# Sheet1.net
KiCad netlist of a schematic drawn in Altium Designer
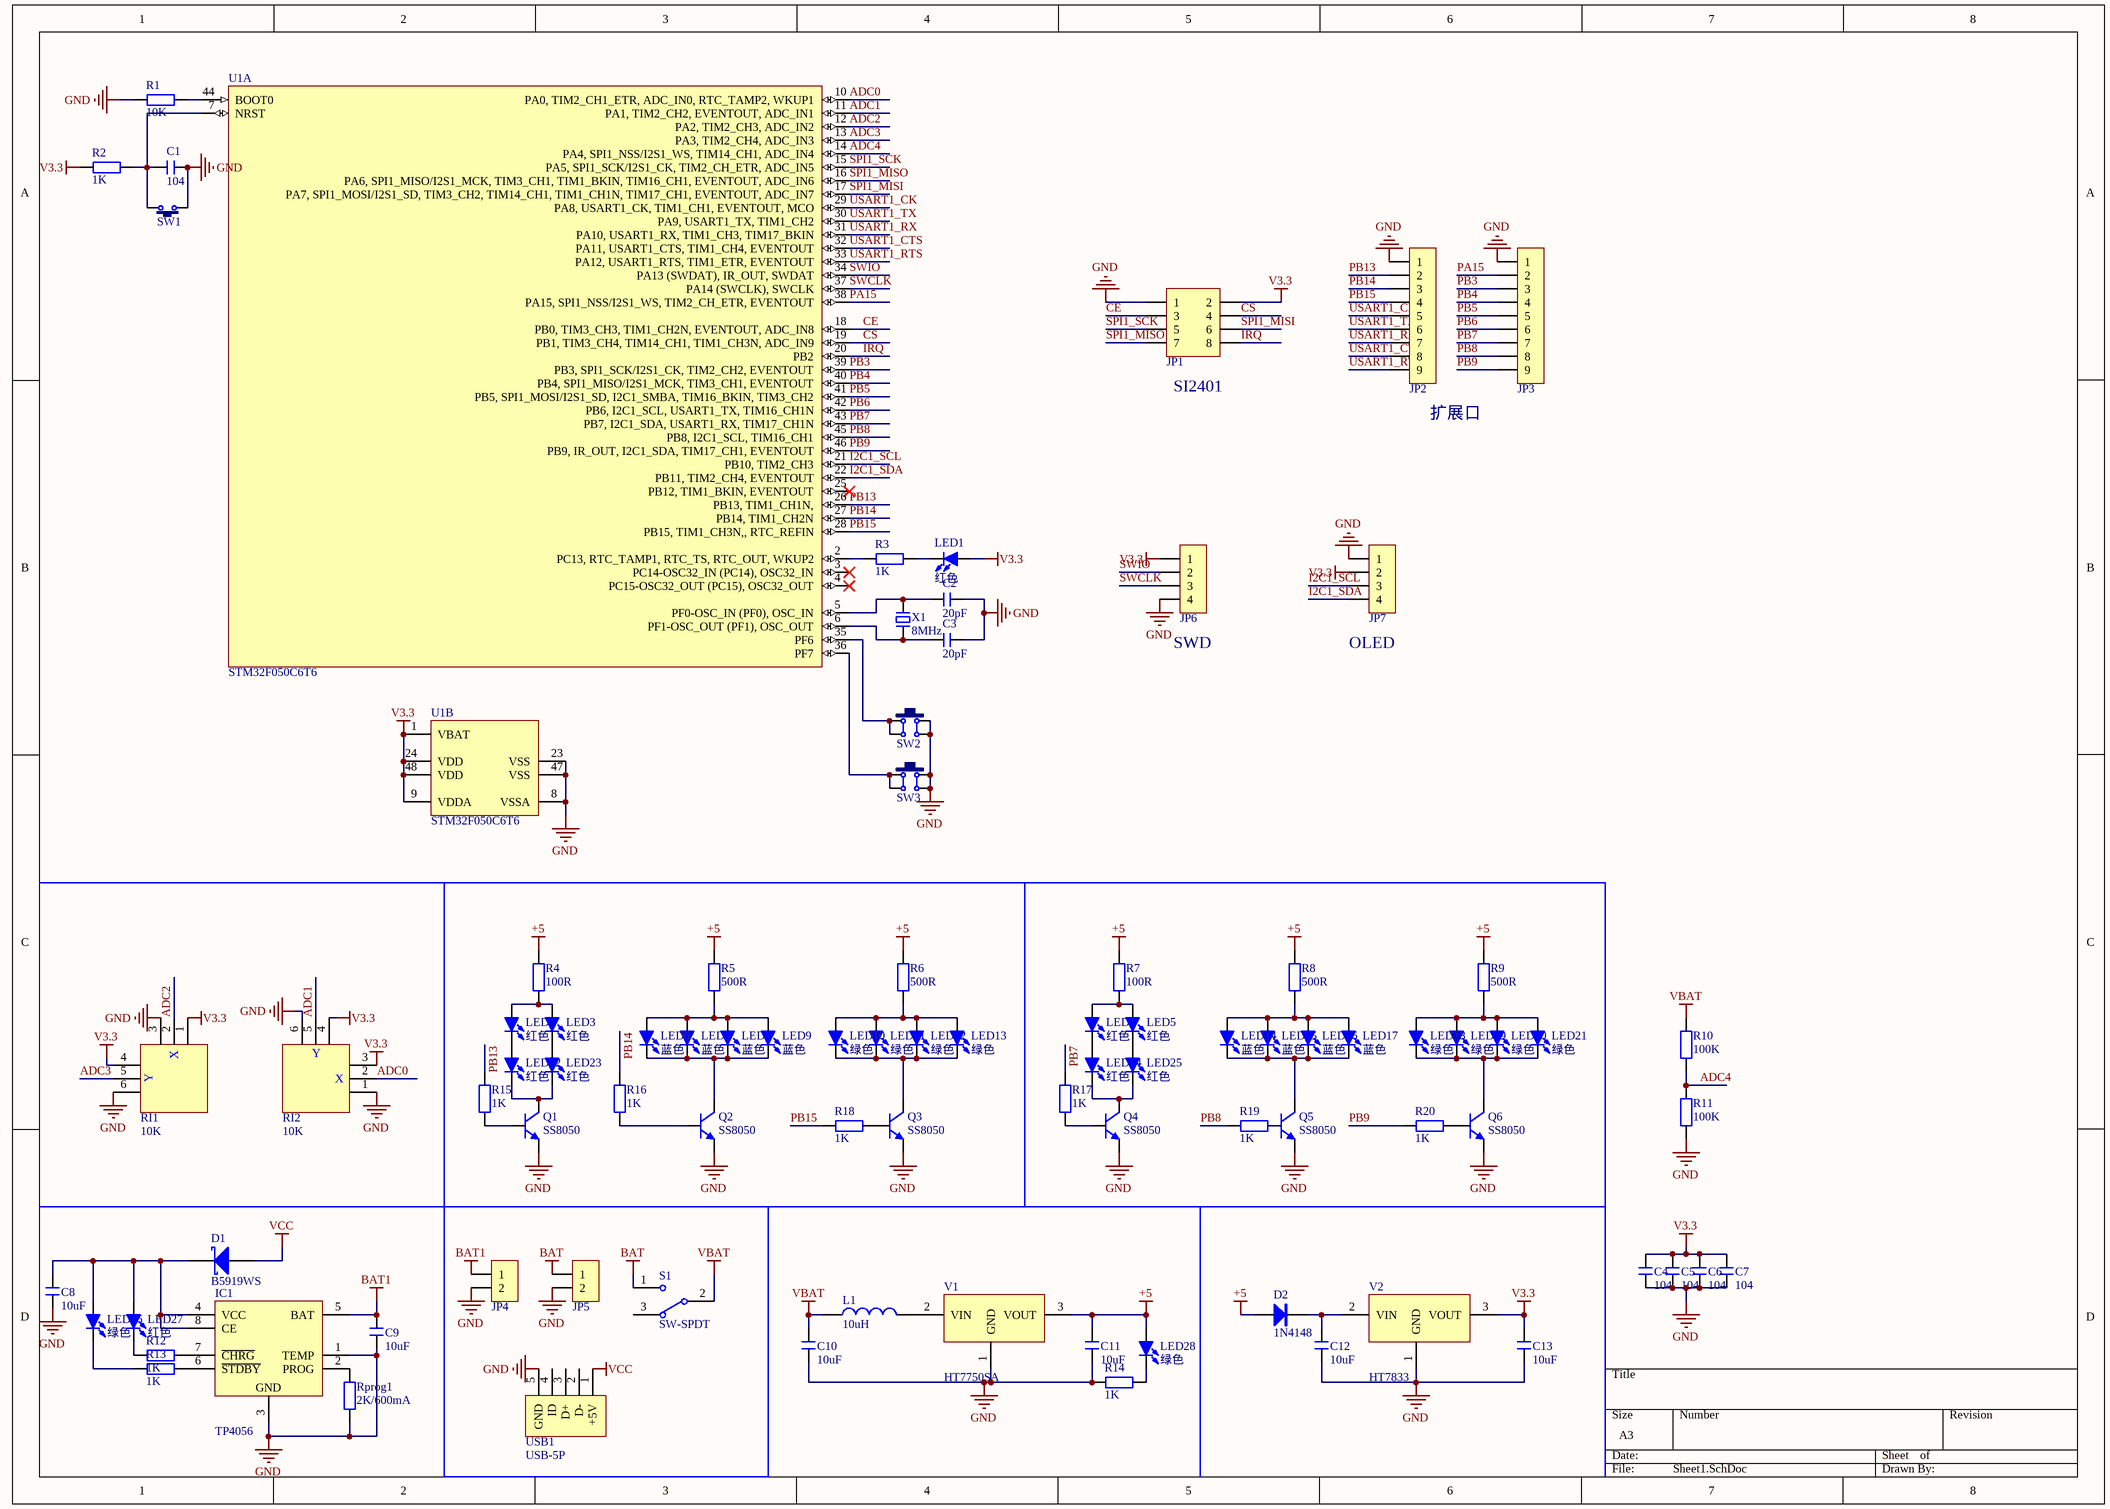
[diagram p0: Sheet1.SchDoc]

(export (version "E")
  (design (tool "Eeschema 10.0.6"))
  (components
    (comp (ref "C1")
      (value "104")
      (footprint "C 0603_L")
      (description "贴片电容")
      (libsource (lib "0.1 - 电阻-电容-电感") (part "C"))
    )
    (comp (ref "C2")
      (value "20pF")
      (footprint "C 0805_L")
      (description "贴片电容")
      (libsource (lib "0.1 - 电阻-电容-电感") (part "C"))
    )
    (comp (ref "C3")
      (value "20pF")
      (footprint "C 0805_L")
      (description "贴片电容")
      (libsource (lib "0.1 - 电阻-电容-电感") (part "C"))
    )
    (comp (ref "C4")
      (value "104")
      (footprint "C 0603_L")
      (description "贴片电容")
      (libsource (lib "0.1 - 电阻-电容-电感") (part "C"))
    )
    (comp (ref "C5")
      (value "104")
      (footprint "C 0603_L")
      (description "贴片电容")
      (libsource (lib "0.1 - 电阻-电容-电感") (part "C"))
    )
    (comp (ref "C6")
      (value "104")
      (footprint "C 0603_L")
      (description "贴片电容")
      (libsource (lib "0.1 - 电阻-电容-电感") (part "C"))
    )
    (comp (ref "C7")
      (value "104")
      (footprint "C 0603_L")
      (description "贴片电容")
      (libsource (lib "0.1 - 电阻-电容-电感") (part "C"))
    )
    (comp (ref "C8")
      (value "10uF")
      (footprint "C 0603_L")
      (description "贴片电容")
      (libsource (lib "0.1 - 电阻-电容-电感") (part "C"))
    )
    (comp (ref "C9")
      (value "10uF")
      (footprint "C 0603_L")
      (description "贴片电容")
      (libsource (lib "0.1 - 电阻-电容-电感") (part "C"))
    )
    (comp (ref "C10")
      (value "10uF")
      (footprint "C 0603_L")
      (description "贴片电容")
      (libsource (lib "0.1 - 电阻-电容-电感") (part "C"))
    )
    (comp (ref "C11")
      (value "10uF")
      (footprint "C 0603_L")
      (description "贴片电容")
      (libsource (lib "0.1 - 电阻-电容-电感") (part "C"))
    )
    (comp (ref "C12")
      (value "10uF")
      (footprint "C 0603_L")
      (description "贴片电容")
      (libsource (lib "0.1 - 电阻-电容-电感") (part "C"))
    )
    (comp (ref "C13")
      (value "10uF")
      (footprint "C 0603_L")
      (description "贴片电容")
      (libsource (lib "0.1 - 电阻-电容-电感") (part "C"))
    )
    (comp (ref "D1")
      (value "B5919WS")
      (footprint "SOD-323")
      (description "肖特基二极管")
      (libsource (lib "0.2 -  二极管-整流桥") (part "1N5819"))
    )
    (comp (ref "D2")
      (value "1N4148")
      (footprint "MINI_MELF (LL34)")
      (description "开关二极管")
      (libsource (lib "0.2 -  二极管-整流桥") (part "1N4148"))
    )
    (comp (ref "IC1")
      (value "TP4056")
      (footprint "SOP8_N")
      (description "锂电池充电管理")
      (libsource (lib "1.1 - 电源类芯片") (part "TP4056"))
    )
    (comp (ref "JP1")
      (value "Header 4X2")
      (footprint "HDR2.54-LI-2x4P")
      (description "4*2P接插件")
      (fields (field (name "版权归属") "封装库来自淘宝 ID：黄晶宝石"))
      (libsource (lib "5.3 - 接插件-脚距2.54 (100mil) ") (part "Header 4X2"))
    )
    (comp (ref "JP2")
      (value "HDR-1X9")
      (footprint "HDR2.54-LI-9P")
      (description "9P接插件")
      (fields (field (name "版权归属") "源创客"))
      (libsource (lib "5.3 - 接插件-脚距2.54 (100mil) ") (part "Header 9"))
    )
    (comp (ref "JP3")
      (value "HDR-1X9")
      (footprint "HDR2.54-LI-9P")
      (description "9P接插件")
      (fields (field (name "版权归属") "源创客"))
      (libsource (lib "5.3 - 接插件-脚距2.54 (100mil) ") (part "Header 9"))
    )
    (comp (ref "JP4")
      (value "HDR-1X2")
      (footprint "XH2.54-LI-2P")
      (description "2P接插件")
      (fields (field (name "版权归属") "封装库来自淘宝 ID：黄晶宝石"))
      (libsource (lib "5.3 - 接插件-脚距2.54 (100mil) ") (part "Header 2"))
    )
    (comp (ref "JP5")
      (value "HDR-1X2")
      (footprint "XH2.54-LI-2P")
      (description "2P接插件")
      (fields (field (name "版权归属") "封装库来自淘宝 ID：黄晶宝石"))
      (libsource (lib "5.3 - 接插件-脚距2.54 (100mil) ") (part "Header 2"))
    )
    (comp (ref "JP6")
      (value "HDR-1X4")
      (footprint "HDR2.54-LI-4P")
      (description "4P接插件")
      (fields (field (name "版权归属") "封装库来自淘宝 ID：黄晶宝石"))
      (libsource (lib "5.3 - 接插件-脚距2.54 (100mil) ") (part "Header 4"))
    )
    (comp (ref "JP7")
      (value "HDR-1X4")
      (footprint "HDR2.54-M-LI-4P")
      (description "4P接插件")
      (fields (field (name "版权归属") "封装库来自淘宝 ID：黄晶宝石"))
      (libsource (lib "5.3 - 接插件-脚距2.54 (100mil) ") (part "Header 4"))
    )
    (comp (ref "L1")
      (value "10uH")
      (footprint "L 0805")
      (description "小功率贴片电感")
      (libsource (lib "0.1 - 电阻-电容-电感") (part "L"))
    )
    (comp (ref "LED1")
      (value "红色")
      (footprint "LED 0603R")
      (description "贴片LED")
      (fields (field (name "版权归属") "封装库来自淘宝 ID：黄晶宝石"))
      (libsource (lib "0.3 - LED发光二极管") (part "LED-SMD"))
    )
    (comp (ref "LED2")
      (value "红色")
      (footprint "LED 0603R")
      (description "贴片LED")
      (fields (field (name "版权归属") "封装库来自淘宝 ID：黄晶宝石"))
      (libsource (lib "0.3 - LED发光二极管") (part "LED-SMD"))
    )
    (comp (ref "LED3")
      (value "红色")
      (footprint "LED 0603R")
      (description "贴片LED")
      (fields (field (name "版权归属") "封装库来自淘宝 ID：黄晶宝石"))
      (libsource (lib "0.3 - LED发光二极管") (part "LED-SMD"))
    )
    (comp (ref "LED4")
      (value "红色")
      (footprint "LED 0603R")
      (description "贴片LED")
      (fields (field (name "版权归属") "封装库来自淘宝 ID：黄晶宝石"))
      (libsource (lib "0.3 - LED发光二极管") (part "LED-SMD"))
    )
    (comp (ref "LED5")
      (value "红色")
      (footprint "LED 0603R")
      (description "贴片LED")
      (fields (field (name "版权归属") "封装库来自淘宝 ID：黄晶宝石"))
      (libsource (lib "0.3 - LED发光二极管") (part "LED-SMD"))
    )
    (comp (ref "LED6")
      (value "蓝色")
      (footprint "LED 0603B")
      (description "贴片LED")
      (fields (field (name "版权归属") "封装库来自淘宝 ID：黄晶宝石"))
      (libsource (lib "0.3 - LED发光二极管") (part "LED-SMD"))
    )
    (comp (ref "LED7")
      (value "蓝色")
      (footprint "LED 0603B")
      (description "贴片LED")
      (fields (field (name "版权归属") "封装库来自淘宝 ID：黄晶宝石"))
      (libsource (lib "0.3 - LED发光二极管") (part "LED-SMD"))
    )
    (comp (ref "LED8")
      (value "蓝色")
      (footprint "LED 0603B")
      (description "贴片LED")
      (fields (field (name "版权归属") "封装库来自淘宝 ID：黄晶宝石"))
      (libsource (lib "0.3 - LED发光二极管") (part "LED-SMD"))
    )
    (comp (ref "LED9")
      (value "蓝色")
      (footprint "LED 0603B")
      (description "贴片LED")
      (fields (field (name "版权归属") "封装库来自淘宝 ID：黄晶宝石"))
      (libsource (lib "0.3 - LED发光二极管") (part "LED-SMD"))
    )
    (comp (ref "LED10")
      (value "绿色")
      (footprint "LED 0603G")
      (description "贴片LED")
      (fields (field (name "版权归属") "封装库来自淘宝 ID：黄晶宝石"))
      (libsource (lib "0.3 - LED发光二极管") (part "LED-SMD"))
    )
    (comp (ref "LED11")
      (value "绿色")
      (footprint "LED 0603G")
      (description "贴片LED")
      (fields (field (name "版权归属") "封装库来自淘宝 ID：黄晶宝石"))
      (libsource (lib "0.3 - LED发光二极管") (part "LED-SMD"))
    )
    (comp (ref "LED12")
      (value "绿色")
      (footprint "LED 0603G")
      (description "贴片LED")
      (fields (field (name "版权归属") "封装库来自淘宝 ID：黄晶宝石"))
      (libsource (lib "0.3 - LED发光二极管") (part "LED-SMD"))
    )
    (comp (ref "LED13")
      (value "绿色")
      (footprint "LED 0603G")
      (description "贴片LED")
      (fields (field (name "版权归属") "封装库来自淘宝 ID：黄晶宝石"))
      (libsource (lib "0.3 - LED发光二极管") (part "LED-SMD"))
    )
    (comp (ref "LED14")
      (value "蓝色")
      (footprint "LED 0603B")
      (description "贴片LED")
      (fields (field (name "版权归属") "封装库来自淘宝 ID：黄晶宝石"))
      (libsource (lib "0.3 - LED发光二极管") (part "LED-SMD"))
    )
    (comp (ref "LED15")
      (value "蓝色")
      (footprint "LED 0603B")
      (description "贴片LED")
      (fields (field (name "版权归属") "封装库来自淘宝 ID：黄晶宝石"))
      (libsource (lib "0.3 - LED发光二极管") (part "LED-SMD"))
    )
    (comp (ref "LED16")
      (value "蓝色")
      (footprint "LED 0603B")
      (description "贴片LED")
      (fields (field (name "版权归属") "封装库来自淘宝 ID：黄晶宝石"))
      (libsource (lib "0.3 - LED发光二极管") (part "LED-SMD"))
    )
    (comp (ref "LED17")
      (value "蓝色")
      (footprint "LED 0603B")
      (description "贴片LED")
      (fields (field (name "版权归属") "封装库来自淘宝 ID：黄晶宝石"))
      (libsource (lib "0.3 - LED发光二极管") (part "LED-SMD"))
    )
    (comp (ref "LED18")
      (value "绿色")
      (footprint "LED 0603G")
      (description "贴片LED")
      (fields (field (name "版权归属") "封装库来自淘宝 ID：黄晶宝石"))
      (libsource (lib "0.3 - LED发光二极管") (part "LED-SMD"))
    )
    (comp (ref "LED19")
      (value "绿色")
      (footprint "LED 0603G")
      (description "贴片LED")
      (fields (field (name "版权归属") "封装库来自淘宝 ID：黄晶宝石"))
      (libsource (lib "0.3 - LED发光二极管") (part "LED-SMD"))
    )
    (comp (ref "LED20")
      (value "绿色")
      (footprint "LED 0603G")
      (description "贴片LED")
      (fields (field (name "版权归属") "封装库来自淘宝 ID：黄晶宝石"))
      (libsource (lib "0.3 - LED发光二极管") (part "LED-SMD"))
    )
    (comp (ref "LED21")
      (value "绿色")
      (footprint "LED 0603G")
      (description "贴片LED")
      (fields (field (name "版权归属") "封装库来自淘宝 ID：黄晶宝石"))
      (libsource (lib "0.3 - LED发光二极管") (part "LED-SMD"))
    )
    (comp (ref "LED22")
      (value "红色")
      (footprint "LED 0603R")
      (description "贴片LED")
      (fields (field (name "版权归属") "封装库来自淘宝 ID：黄晶宝石"))
      (libsource (lib "0.3 - LED发光二极管") (part "LED-SMD"))
    )
    (comp (ref "LED23")
      (value "红色")
      (footprint "LED 0603R")
      (description "贴片LED")
      (fields (field (name "版权归属") "封装库来自淘宝 ID：黄晶宝石"))
      (libsource (lib "0.3 - LED发光二极管") (part "LED-SMD"))
    )
    (comp (ref "LED24")
      (value "红色")
      (footprint "LED 0603R")
      (description "贴片LED")
      (fields (field (name "版权归属") "封装库来自淘宝 ID：黄晶宝石"))
      (libsource (lib "0.3 - LED发光二极管") (part "LED-SMD"))
    )
    (comp (ref "LED25")
      (value "红色")
      (footprint "LED 0603R")
      (description "贴片LED")
      (fields (field (name "版权归属") "封装库来自淘宝 ID：黄晶宝石"))
      (libsource (lib "0.3 - LED发光二极管") (part "LED-SMD"))
    )
    (comp (ref "LED26")
      (value "绿色")
      (footprint "LED 0603G")
      (description "贴片LED")
      (fields (field (name "版权归属") "封装库来自淘宝 ID：黄晶宝石"))
      (libsource (lib "0.3 - LED发光二极管") (part "LED-SMD"))
    )
    (comp (ref "LED27")
      (value "红色")
      (footprint "LED 0603R")
      (description "贴片LED")
      (fields (field (name "版权归属") "封装库来自淘宝 ID：黄晶宝石"))
      (libsource (lib "0.3 - LED发光二极管") (part "LED-SMD"))
    )
    (comp (ref "LED28")
      (value "绿色")
      (footprint "LED 0603G")
      (description "贴片LED")
      (fields (field (name "版权归属") "封装库来自淘宝 ID：黄晶宝石"))
      (libsource (lib "0.3 - LED发光二极管") (part "LED-SMD"))
    )
    (comp (ref "Q1")
      (value "SS8050")
      (footprint "SOT23-3N")
      (description "高频放大-NPN型")
      (fields (field (name "版权归属") "封装库来自淘宝 ID：黄晶宝石"))
      (libsource (lib "0.4 - 三极管") (part "8050-SMD"))
    )
    (comp (ref "Q2")
      (value "SS8050")
      (footprint "SOT23-3N")
      (description "高频放大-NPN型")
      (fields (field (name "版权归属") "封装库来自淘宝 ID：黄晶宝石"))
      (libsource (lib "0.4 - 三极管") (part "8050-SMD"))
    )
    (comp (ref "Q3")
      (value "SS8050")
      (footprint "SOT23-3N")
      (description "高频放大-NPN型")
      (fields (field (name "版权归属") "封装库来自淘宝 ID：黄晶宝石"))
      (libsource (lib "0.4 - 三极管") (part "8050-SMD"))
    )
    (comp (ref "Q4")
      (value "SS8050")
      (footprint "SOT23-3N")
      (description "高频放大-NPN型")
      (fields (field (name "版权归属") "封装库来自淘宝 ID：黄晶宝石"))
      (libsource (lib "0.4 - 三极管") (part "8050-SMD"))
    )
    (comp (ref "Q5")
      (value "SS8050")
      (footprint "SOT23-3N")
      (description "高频放大-NPN型")
      (fields (field (name "版权归属") "封装库来自淘宝 ID：黄晶宝石"))
      (libsource (lib "0.4 - 三极管") (part "8050-SMD"))
    )
    (comp (ref "Q6")
      (value "SS8050")
      (footprint "SOT23-3N")
      (description "高频放大-NPN型")
      (fields (field (name "版权归属") "封装库来自淘宝 ID：黄晶宝石"))
      (libsource (lib "0.4 - 三极管") (part "8050-SMD"))
    )
    (comp (ref "R1")
      (value "10K")
      (footprint "R 0603_L")
      (description "贴片电阻")
      (fields (field (name "版权归属") "来自淘宝 ID：黄晶宝石"))
      (libsource (lib "0.1 - 电阻-电容-电感") (part "R"))
    )
    (comp (ref "R2")
      (value "1K")
      (footprint "R 0603_L")
      (description "贴片电阻")
      (fields (field (name "版权归属") "来自淘宝 ID：黄晶宝石"))
      (libsource (lib "0.1 - 电阻-电容-电感") (part "R"))
    )
    (comp (ref "R3")
      (value "1K")
      (footprint "R 0603_L")
      (description "贴片电阻")
      (fields (field (name "版权归属") "来自淘宝 ID：黄晶宝石"))
      (libsource (lib "0.1 - 电阻-电容-电感") (part "R"))
    )
    (comp (ref "R4")
      (value "100R")
      (footprint "R 0603_L")
      (description "贴片电阻")
      (fields (field (name "版权归属") "来自淘宝 ID：黄晶宝石"))
      (libsource (lib "0.1 - 电阻-电容-电感") (part "R"))
    )
    (comp (ref "R5")
      (value "500R")
      (footprint "R 0603_L")
      (description "贴片电阻")
      (fields (field (name "版权归属") "来自淘宝 ID：黄晶宝石"))
      (libsource (lib "0.1 - 电阻-电容-电感") (part "R"))
    )
    (comp (ref "R6")
      (value "500R")
      (footprint "R 0603_L")
      (description "贴片电阻")
      (fields (field (name "版权归属") "来自淘宝 ID：黄晶宝石"))
      (libsource (lib "0.1 - 电阻-电容-电感") (part "R"))
    )
    (comp (ref "R7")
      (value "100R")
      (footprint "R 0603_L")
      (description "贴片电阻")
      (fields (field (name "版权归属") "来自淘宝 ID：黄晶宝石"))
      (libsource (lib "0.1 - 电阻-电容-电感") (part "R"))
    )
    (comp (ref "R8")
      (value "500R")
      (footprint "R 0603_L")
      (description "贴片电阻")
      (fields (field (name "版权归属") "来自淘宝 ID：黄晶宝石"))
      (libsource (lib "0.1 - 电阻-电容-电感") (part "R"))
    )
    (comp (ref "R9")
      (value "500R")
      (footprint "R 0603_L")
      (description "贴片电阻")
      (fields (field (name "版权归属") "来自淘宝 ID：黄晶宝石"))
      (libsource (lib "0.1 - 电阻-电容-电感") (part "R"))
    )
    (comp (ref "R10")
      (value "100K")
      (footprint "R 0603_L")
      (description "贴片电阻")
      (fields (field (name "版权归属") "来自淘宝 ID：黄晶宝石"))
      (libsource (lib "0.1 - 电阻-电容-电感") (part "R"))
    )
    (comp (ref "R11")
      (value "100K")
      (footprint "R 0603_L")
      (description "贴片电阻")
      (fields (field (name "版权归属") "来自淘宝 ID：黄晶宝石"))
      (libsource (lib "0.1 - 电阻-电容-电感") (part "R"))
    )
    (comp (ref "R12")
      (value "1K")
      (footprint "R 0603_L")
      (description "贴片电阻")
      (fields (field (name "版权归属") "来自淘宝 ID：黄晶宝石"))
      (libsource (lib "0.1 - 电阻-电容-电感") (part "R"))
    )
    (comp (ref "R13")
      (value "1K")
      (footprint "R 0603_L")
      (description "贴片电阻")
      (fields (field (name "版权归属") "来自淘宝 ID：黄晶宝石"))
      (libsource (lib "0.1 - 电阻-电容-电感") (part "R"))
    )
    (comp (ref "R14")
      (value "1K")
      (footprint "R 0603_L")
      (description "贴片电阻")
      (fields (field (name "版权归属") "来自淘宝 ID：黄晶宝石"))
      (libsource (lib "0.1 - 电阻-电容-电感") (part "R"))
    )
    (comp (ref "R15")
      (value "1K")
      (footprint "R 0603_L")
      (description "贴片电阻")
      (fields (field (name "版权归属") "来自淘宝 ID：黄晶宝石"))
      (libsource (lib "0.1 - 电阻-电容-电感") (part "R"))
    )
    (comp (ref "R16")
      (value "1K")
      (footprint "R 0603_L")
      (description "贴片电阻")
      (fields (field (name "版权归属") "来自淘宝 ID：黄晶宝石"))
      (libsource (lib "0.1 - 电阻-电容-电感") (part "R"))
    )
    (comp (ref "R17")
      (value "1K")
      (footprint "R 0603_L")
      (description "贴片电阻")
      (fields (field (name "版权归属") "来自淘宝 ID：黄晶宝石"))
      (libsource (lib "0.1 - 电阻-电容-电感") (part "R"))
    )
    (comp (ref "R18")
      (value "1K")
      (footprint "R 0603_L")
      (description "贴片电阻")
      (fields (field (name "版权归属") "来自淘宝 ID：黄晶宝石"))
      (libsource (lib "0.1 - 电阻-电容-电感") (part "R"))
    )
    (comp (ref "R19")
      (value "1K")
      (footprint "R 0603_L")
      (description "贴片电阻")
      (fields (field (name "版权归属") "来自淘宝 ID：黄晶宝石"))
      (libsource (lib "0.1 - 电阻-电容-电感") (part "R"))
    )
    (comp (ref "R20")
      (value "1K")
      (footprint "R 0603_L")
      (description "贴片电阻")
      (fields (field (name "版权归属") "来自淘宝 ID：黄晶宝石"))
      (libsource (lib "0.1 - 电阻-电容-电感") (part "R"))
    )
    (comp (ref "RI1")
      (value "10K")
      (footprint "ROC16")
      (description "摇杆电位器")
      (fields (field (name "版权归属") "封装库来自淘宝 ID：黄晶宝石"))
      (libsource (lib "") (part "ROC16B_1"))
    )
    (comp (ref "RI2")
      (value "10K")
      (footprint "ROC16")
      (description "摇杆电位器")
      (fields (field (name "版权归属") "封装库来自淘宝 ID：黄晶宝石"))
      (libsource (lib "1.2 - 传感元件") (part "ROC16B"))
    )
    (comp (ref "Rprog1")
      (value "2K/600mA")
      (footprint "R 0603_M")
      (description "贴片电阻")
      (fields (field (name "版权归属") "来自淘宝 ID：黄晶宝石"))
      (libsource (lib "0.1 - 电阻-电容-电感") (part "R"))
    )
    (comp (ref "S1")
      (value "SW-SPDT")
      (footprint "SWITCH_PWR")
      (description "SPDT Subminiature Toggle Switch, Right Angle Mounting, Vertical Actuation")
      (fields (field (name "PUBLISHER") "mazhongwei"))
      (libsource (lib "RoboFly") (part "SW-SPDT"))
    )
    (comp (ref "SW1")
      (value "3x6x5")
      (footprint "TSW SMD-3*6*2.5")
      (description "3x6轻触开关")
      (fields (field (name "版权归属") "封装库来自淘宝 ID：黄晶宝石"))
      (libsource (lib "0.7 - 常用按键-开关") (part "TSW 3x6"))
    )
    (comp (ref "SW2")
      (value "6x6x5")
      (footprint "TSW DIP-6*6*6")
      (description "直插6x6轻触开关")
      (fields (field (name "版权归属") "封装库来自淘宝 ID：黄晶宝石"))
      (libsource (lib "0.7 - 常用按键-开关") (part "TSW DIP-6x6"))
    )
    (comp (ref "SW3")
      (value "6x6x5")
      (footprint "TSW DIP-6*6*6")
      (description "直插6x6轻触开关")
      (fields (field (name "版权归属") "封装库来自淘宝 ID：黄晶宝石"))
      (libsource (lib "0.7 - 常用按键-开关") (part "TSW DIP-6x6"))
    )
    (comp (ref "U1")
      (value "STM32F050C6T6")
      (footprint "LQFP48_N")
      (libsource (lib "2.2 - STM32 F0系列MCU 集成库") (part "STM32F050C6T6"))
    )
    (comp (ref "USB1")
      (value "USB-5P")
      (footprint "USB-MICRO_D")
      (description "微型USB母座")
      (libsource (lib "0.8 - 网口-音频插座") (part "USB-5P"))
    )
    (comp (ref "V1")
      (value "HT7750SA")
      (footprint "SOT89_M")
      (description "LDO线性稳压芯片")
      (fields (field (name "版权归属") "封装库来自淘宝 ID：黄晶宝石"))
      (libsource (lib "1.1 - 电源类芯片") (part "HT71xx"))
    )
    (comp (ref "V2")
      (value "HT7833")
      (footprint "SOT89_M")
      (description "LDO线性稳压芯片")
      (fields (field (name "版权归属") "封装库来自淘宝 ID：黄晶宝石"))
      (libsource (lib "1.1 - 电源类芯片") (part "HT71xx"))
    )
    (comp (ref "X1")
      (value "8MHz")
      (footprint "OSC HC-49S")
      (description "2脚无源脚晶振")
      (fields (field (name "版权归属") "源创客"))
      (libsource (lib "2.0 - 保险丝-晶振-光耦") (part "XTAL-2P"))
    )
  )
  (nets
    (net (code "1") (name "+5") (class "Default")
      (node (ref "C11") (pin "2") (pinfunction "2_2") (pintype "passive"))
      (node (ref "D2") (pin "1") (pinfunction "A_1") (pintype "passive"))
      (node (ref "LED28") (pin "1") (pinfunction "A_1") (pintype "passive"))
      (node (ref "R4") (pin "2") (pinfunction "2_2") (pintype "passive"))
      (node (ref "R5") (pin "2") (pinfunction "2_2") (pintype "passive"))
      (node (ref "R6") (pin "2") (pinfunction "2_2") (pintype "passive"))
      (node (ref "R7") (pin "2") (pinfunction "2_2") (pintype "passive"))
      (node (ref "R8") (pin "2") (pinfunction "2_2") (pintype "passive"))
      (node (ref "R9") (pin "2") (pinfunction "2_2") (pintype "passive"))
      (node (ref "V1") (pin "3") (pinfunction "VOUT_3") (pintype "passive"))
    )
    (net (code "2") (name "/ADC0") (class "Default")
      (node (ref "RI2") (pin "2") (pinfunction "2_2") (pintype "passive"))
      (node (ref "U1") (pin "10") (pinfunction "PA0,_TIM2_CH1_ETR,_ADC_IN0,_RTC_TAMP2,_WKUP1_10") (pintype "bidirectional"))
    )
    (net (code "3") (name "/ADC1") (class "Default")
      (node (ref "RI2") (pin "5") (pinfunction "5_5") (pintype "passive"))
      (node (ref "U1") (pin "11") (pinfunction "PA1,_TIM2_CH2,_EVENTOUT,_ADC_IN1_11") (pintype "bidirectional"))
    )
    (net (code "4") (name "/ADC2") (class "Default")
      (node (ref "RI1") (pin "2") (pinfunction "2_2") (pintype "passive"))
      (node (ref "U1") (pin "12") (pinfunction "PA2,_TIM2_CH3,_ADC_IN2_12") (pintype "bidirectional"))
    )
    (net (code "5") (name "/ADC3") (class "Default")
      (node (ref "RI1") (pin "5") (pinfunction "5_5") (pintype "passive"))
      (node (ref "U1") (pin "13") (pinfunction "PA3,_TIM2_CH4,_ADC_IN3_13") (pintype "bidirectional"))
    )
    (net (code "6") (name "/ADC4") (class "Default")
      (node (ref "R10") (pin "1") (pinfunction "1_1") (pintype "passive"))
      (node (ref "R11") (pin "2") (pinfunction "2_2") (pintype "passive"))
      (node (ref "U1") (pin "14") (pinfunction "PA4,_SPI1_NSS/I2S1_WS,_TIM14_CH1,_ADC_IN4_14") (pintype "bidirectional"))
    )
    (net (code "7") (name "/CE") (class "Default")
      (node (ref "JP1") (pin "3") (pinfunction "3_3") (pintype "passive"))
      (node (ref "U1") (pin "18") (pinfunction "PB0,_TIM3_CH3,_TIM1_CH2N,_EVENTOUT,_ADC_IN8_18") (pintype "bidirectional"))
    )
    (net (code "8") (name "/CS") (class "Default")
      (node (ref "JP1") (pin "4") (pinfunction "4_4") (pintype "passive"))
      (node (ref "U1") (pin "19") (pinfunction "PB1,_TIM3_CH4,_TIM14_CH1,_TIM1_CH3N,_ADC_IN9_19") (pintype "bidirectional"))
    )
    (net (code "9") (name "/I2C1_SCL") (class "Default")
      (node (ref "JP7") (pin "3") (pinfunction "3_3") (pintype "passive"))
      (node (ref "U1") (pin "21") (pinfunction "PB10,_TIM2_CH3_21") (pintype "bidirectional"))
    )
    (net (code "10") (name "/I2C1_SDA") (class "Default")
      (node (ref "JP7") (pin "4") (pinfunction "4_4") (pintype "passive"))
      (node (ref "U1") (pin "22") (pinfunction "PB11,_TIM2_CH4,_EVENTOUT_22") (pintype "bidirectional"))
    )
    (net (code "11") (name "/IRQ") (class "Default")
      (node (ref "JP1") (pin "8") (pinfunction "8_8") (pintype "passive"))
      (node (ref "U1") (pin "20") (pinfunction "PB2_20") (pintype "bidirectional"))
    )
    (net (code "12") (name "/PA15") (class "Default")
      (node (ref "JP3") (pin "2") (pinfunction "2_2") (pintype "passive"))
      (node (ref "U1") (pin "38") (pinfunction "PA15,_SPI1_NSS/I2S1_WS,_TIM2_CH_ETR,_EVENTOUT_38") (pintype "bidirectional"))
    )
    (net (code "13") (name "/PB3") (class "Default")
      (node (ref "JP3") (pin "3") (pinfunction "3_3") (pintype "passive"))
      (node (ref "U1") (pin "39") (pinfunction "PB3,_SPI1_SCK/I2S1_CK,_TIM2_CH2,_EVENTOUT_39") (pintype "bidirectional"))
    )
    (net (code "14") (name "/PB4") (class "Default")
      (node (ref "JP3") (pin "4") (pinfunction "4_4") (pintype "passive"))
      (node (ref "U1") (pin "40") (pinfunction "PB4,_SPI1_MISO/I2S1_MCK,_TIM3_CH1,_EVENTOUT_40") (pintype "bidirectional"))
    )
    (net (code "15") (name "/PB5") (class "Default")
      (node (ref "JP3") (pin "5") (pinfunction "5_5") (pintype "passive"))
      (node (ref "U1") (pin "41") (pinfunction "PB5,_SPI1_MOSI/I2S1_SD,_I2C1_SMBA,_TIM16_BKIN,_TIM3_CH2_41") (pintype "bidirectional"))
    )
    (net (code "16") (name "/PB6") (class "Default")
      (node (ref "JP3") (pin "6") (pinfunction "6_6") (pintype "passive"))
      (node (ref "U1") (pin "42") (pinfunction "PB6,_I2C1_SCL,_USART1_TX,_TIM16_CH1N_42") (pintype "bidirectional"))
    )
    (net (code "17") (name "/PB7") (class "Default")
      (node (ref "JP3") (pin "7") (pinfunction "7_7") (pintype "passive"))
      (node (ref "R17") (pin "2") (pinfunction "2_2") (pintype "passive"))
      (node (ref "U1") (pin "43") (pinfunction "PB7,_I2C1_SDA,_USART1_RX,_TIM17_CH1N_43") (pintype "bidirectional"))
    )
    (net (code "18") (name "/PB8") (class "Default")
      (node (ref "JP3") (pin "8") (pinfunction "8_8") (pintype "passive"))
      (node (ref "R19") (pin "2") (pinfunction "2_2") (pintype "passive"))
      (node (ref "U1") (pin "45") (pinfunction "PB8,_I2C1_SCL,_TIM16_CH1_45") (pintype "bidirectional"))
    )
    (net (code "19") (name "/PB9") (class "Default")
      (node (ref "JP3") (pin "9") (pinfunction "9_9") (pintype "passive"))
      (node (ref "R20") (pin "2") (pinfunction "2_2") (pintype "passive"))
      (node (ref "U1") (pin "46") (pinfunction "PB9,_IR_OUT,_I2C1_SDA,_TIM17_CH1,_EVENTOUT_46") (pintype "bidirectional"))
    )
    (net (code "20") (name "/PB13") (class "Default")
      (node (ref "JP2") (pin "2") (pinfunction "2_2") (pintype "passive"))
      (node (ref "R15") (pin "2") (pinfunction "2_2") (pintype "passive"))
      (node (ref "U1") (pin "26") (pinfunction "PB13,_TIM1_CH1N,_26") (pintype "bidirectional"))
    )
    (net (code "21") (name "/PB14") (class "Default")
      (node (ref "JP2") (pin "3") (pinfunction "3_3") (pintype "passive"))
      (node (ref "R16") (pin "2") (pinfunction "2_2") (pintype "passive"))
      (node (ref "U1") (pin "27") (pinfunction "PB14,_TIM1_CH2N_27") (pintype "bidirectional"))
    )
    (net (code "22") (name "/PB15") (class "Default")
      (node (ref "JP2") (pin "4") (pinfunction "4_4") (pintype "passive"))
      (node (ref "R18") (pin "2") (pinfunction "2_2") (pintype "passive"))
      (node (ref "U1") (pin "28") (pinfunction "PB15,_TIM1_CH3N,,_RTC_REFIN_28") (pintype "bidirectional"))
    )
    (net (code "23") (name "/SPI1_MISI") (class "Default")
      (node (ref "JP1") (pin "6") (pinfunction "6_6") (pintype "passive"))
      (node (ref "U1") (pin "17") (pinfunction "PA7,_SPI1_MOSI/I2S1_SD,_TIM3_CH2,_TIM14_CH1,_TIM1_CH1N,_TIM17_CH1,_EVENTOUT,_ADC_IN7_17") (pintype "bidirectional"))
    )
    (net (code "24") (name "/SPI1_MISO") (class "Default")
      (node (ref "JP1") (pin "7") (pinfunction "7_7") (pintype "passive"))
      (node (ref "U1") (pin "16") (pinfunction "PA6,_SPI1_MISO/I2S1_MCK,_TIM3_CH1,_TIM1_BKIN,_TIM16_CH1,_EVENTOUT,_ADC_IN6_16") (pintype "bidirectional"))
    )
    (net (code "25") (name "/SPI1_SCK") (class "Default")
      (node (ref "JP1") (pin "5") (pinfunction "5_5") (pintype "passive"))
      (node (ref "U1") (pin "15") (pinfunction "PA5,_SPI1_SCK/I2S1_CK,_TIM2_CH_ETR,_ADC_IN5_15") (pintype "bidirectional"))
    )
    (net (code "26") (name "/SWCLK") (class "Default")
      (node (ref "JP6") (pin "3") (pinfunction "3_3") (pintype "passive"))
      (node (ref "U1") (pin "37") (pinfunction "PA14_(SWCLK),_SWCLK_37") (pintype "bidirectional"))
    )
    (net (code "27") (name "/SWIO") (class "Default")
      (node (ref "JP6") (pin "2") (pinfunction "2_2") (pintype "passive"))
      (node (ref "U1") (pin "34") (pinfunction "PA13_(SWDAT),_IR_OUT,_SWDAT_34") (pintype "bidirectional"))
    )
    (net (code "28") (name "/USART1_CK") (class "Default")
      (node (ref "JP2") (pin "5") (pinfunction "5_5") (pintype "passive"))
      (node (ref "U1") (pin "29") (pinfunction "PA8,_USART1_CK,_TIM1_CH1,_EVENTOUT,_MCO_29") (pintype "bidirectional"))
    )
    (net (code "29") (name "/USART1_CTS") (class "Default")
      (node (ref "JP2") (pin "8") (pinfunction "8_8") (pintype "passive"))
      (node (ref "U1") (pin "32") (pinfunction "PA11,_USART1_CTS,_TIM1_CH4,_EVENTOUT_32") (pintype "bidirectional"))
    )
    (net (code "30") (name "/USART1_RTS") (class "Default")
      (node (ref "JP2") (pin "9") (pinfunction "9_9") (pintype "passive"))
      (node (ref "U1") (pin "33") (pinfunction "PA12,_USART1_RTS,_TIM1_ETR,_EVENTOUT_33") (pintype "bidirectional"))
    )
    (net (code "31") (name "/USART1_RX") (class "Default")
      (node (ref "JP2") (pin "7") (pinfunction "7_7") (pintype "passive"))
      (node (ref "U1") (pin "31") (pinfunction "PA10,_USART1_RX,_TIM1_CH3,_TIM17_BKIN_31") (pintype "bidirectional"))
    )
    (net (code "32") (name "/USART1_TX") (class "Default")
      (node (ref "JP2") (pin "6") (pinfunction "6_6") (pintype "passive"))
      (node (ref "U1") (pin "30") (pinfunction "PA9,_USART1_TX,_TIM1_CH2_30") (pintype "bidirectional"))
    )
    (net (code "33") (name "BAT") (class "Default")
      (node (ref "JP5") (pin "1") (pinfunction "1_1") (pintype "passive"))
      (node (ref "S1") (pin "1") (pinfunction "1_1") (pintype "passive"))
    )
    (net (code "34") (name "BAT1") (class "Default")
      (node (ref "C9") (pin "2") (pinfunction "2_2") (pintype "passive"))
      (node (ref "IC1") (pin "5") (pinfunction "BAT_5") (pintype "passive"))
      (node (ref "JP4") (pin "1") (pinfunction "1_1") (pintype "passive"))
    )
    (net (code "35") (name "GND") (class "Default")
      (node (ref "C1") (pin "1") (pinfunction "1_1") (pintype "passive"))
      (node (ref "C10") (pin "1") (pinfunction "1_1") (pintype "passive"))
      (node (ref "C11") (pin "1") (pinfunction "1_1") (pintype "passive"))
      (node (ref "C12") (pin "1") (pinfunction "1_1") (pintype "passive"))
      (node (ref "C13") (pin "1") (pinfunction "1_1") (pintype "passive"))
      (node (ref "C2") (pin "2") (pinfunction "2_2") (pintype "passive"))
      (node (ref "C3") (pin "2") (pinfunction "2_2") (pintype "passive"))
      (node (ref "C4") (pin "1") (pinfunction "1_1") (pintype "passive"))
      (node (ref "C5") (pin "1") (pinfunction "1_1") (pintype "passive"))
      (node (ref "C6") (pin "1") (pinfunction "1_1") (pintype "passive"))
      (node (ref "C7") (pin "1") (pinfunction "1_1") (pintype "passive"))
      (node (ref "C8") (pin "1") (pinfunction "1_1") (pintype "passive"))
      (node (ref "C9") (pin "1") (pinfunction "1_1") (pintype "passive"))
      (node (ref "IC1") (pin "1") (pinfunction "TEMP_1") (pintype "passive"))
      (node (ref "IC1") (pin "3") (pinfunction "GND_3") (pintype "passive"))
      (node (ref "JP1") (pin "1") (pinfunction "1_1") (pintype "passive"))
      (node (ref "JP2") (pin "1") (pinfunction "1_1") (pintype "passive"))
      (node (ref "JP3") (pin "1") (pinfunction "1_1") (pintype "passive"))
      (node (ref "JP4") (pin "2") (pinfunction "2_2") (pintype "passive"))
      (node (ref "JP5") (pin "2") (pinfunction "2_2") (pintype "passive"))
      (node (ref "JP6") (pin "4") (pinfunction "4_4") (pintype "passive"))
      (node (ref "JP7") (pin "1") (pinfunction "1_1") (pintype "passive"))
      (node (ref "Q1") (pin "2") (pinfunction "E_2") (pintype "passive"))
      (node (ref "Q2") (pin "2") (pinfunction "E_2") (pintype "passive"))
      (node (ref "Q3") (pin "2") (pinfunction "E_2") (pintype "passive"))
      (node (ref "Q4") (pin "2") (pinfunction "E_2") (pintype "passive"))
      (node (ref "Q5") (pin "2") (pinfunction "E_2") (pintype "passive"))
      (node (ref "Q6") (pin "2") (pinfunction "E_2") (pintype "passive"))
      (node (ref "R1") (pin "1") (pinfunction "1_1") (pintype "passive"))
      (node (ref "R11") (pin "1") (pinfunction "1_1") (pintype "passive"))
      (node (ref "R14") (pin "1") (pinfunction "1_1") (pintype "passive"))
      (node (ref "RI1") (pin "3") (pinfunction "3_3") (pintype "passive"))
      (node (ref "RI1") (pin "6") (pinfunction "6_6") (pintype "passive"))
      (node (ref "RI2") (pin "1") (pinfunction "1_1") (pintype "passive"))
      (node (ref "RI2") (pin "6") (pinfunction "6_6") (pintype "passive"))
      (node (ref "Rprog1") (pin "1") (pinfunction "1_1") (pintype "passive"))
      (node (ref "SW1") (pin "1") (pinfunction "1_1") (pintype "passive"))
      (node (ref "SW2") (pin "2") (pinfunction "2_2") (pintype "passive"))
      (node (ref "SW2") (pin "3") (pinfunction "3_3") (pintype "passive"))
      (node (ref "SW3") (pin "2") (pinfunction "2_2") (pintype "passive"))
      (node (ref "SW3") (pin "3") (pinfunction "3_3") (pintype "passive"))
      (node (ref "U1") (pin "23") (pinfunction "VSS_23") (pintype "power_in"))
      (node (ref "U1") (pin "47") (pinfunction "VSS_47") (pintype "power_in"))
      (node (ref "U1") (pin "8") (pinfunction "VSSA_8") (pintype "power_in"))
      (node (ref "USB1") (pin "5") (pinfunction "GND_5") (pintype "passive"))
      (node (ref "V1") (pin "1") (pinfunction "GND_1") (pintype "passive"))
      (node (ref "V2") (pin "1") (pinfunction "GND_1") (pintype "passive"))
    )
    (net (code "36") (name "Net-(D1-K)") (class "Default")
      (node (ref "C8") (pin "2") (pinfunction "2_2") (pintype "passive"))
      (node (ref "D1") (pin "2") (pinfunction "K_2") (pintype "passive"))
      (node (ref "IC1") (pin "4") (pinfunction "VCC_4") (pintype "passive"))
      (node (ref "IC1") (pin "8") (pinfunction "CE_8") (pintype "passive"))
      (node (ref "LED26") (pin "1") (pinfunction "A_1") (pintype "passive"))
      (node (ref "LED27") (pin "1") (pinfunction "A_1") (pintype "passive"))
    )
    (net (code "37") (name "Net-(D2-K)") (class "Default")
      (node (ref "C12") (pin "2") (pinfunction "2_2") (pintype "passive"))
      (node (ref "D2") (pin "2") (pinfunction "K_2") (pintype "passive"))
      (node (ref "V2") (pin "2") (pinfunction "VIN_2") (pintype "passive"))
    )
    (net (code "38") (name "Net-(IC1-PROG)") (class "Default")
      (node (ref "IC1") (pin "2") (pinfunction "PROG_2") (pintype "passive"))
      (node (ref "Rprog1") (pin "2") (pinfunction "2_2") (pintype "passive"))
    )
    (net (code "39") (name "Net-(IC1-~{CHRG})") (class "Default")
      (node (ref "IC1") (pin "7") (pinfunction "~{CHRG}_7") (pintype "passive"))
      (node (ref "R12") (pin "1") (pinfunction "1_1") (pintype "passive"))
    )
    (net (code "40") (name "Net-(IC1-~{STDBY})") (class "Default")
      (node (ref "IC1") (pin "6") (pinfunction "~{STDBY}_6") (pintype "passive"))
      (node (ref "R13") (pin "2") (pinfunction "2_2") (pintype "passive"))
    )
    (net (code "41") (name "Net-(LED1-K)") (class "Default")
      (node (ref "LED1") (pin "2") (pinfunction "K_2") (pintype "passive"))
      (node (ref "R3") (pin "1") (pinfunction "1_1") (pintype "passive"))
    )
    (net (code "42") (name "Net-(LED2-A)") (class "Default")
      (node (ref "LED2") (pin "1") (pinfunction "A_1") (pintype "passive"))
      (node (ref "LED3") (pin "1") (pinfunction "A_1") (pintype "passive"))
      (node (ref "R4") (pin "1") (pinfunction "1_1") (pintype "passive"))
    )
    (net (code "43") (name "Net-(LED2-K)") (class "Default")
      (node (ref "LED2") (pin "2") (pinfunction "K_2") (pintype "passive"))
      (node (ref "LED22") (pin "1") (pinfunction "A_1") (pintype "passive"))
    )
    (net (code "44") (name "Net-(LED4-A)") (class "Default")
      (node (ref "LED4") (pin "1") (pinfunction "A_1") (pintype "passive"))
      (node (ref "LED5") (pin "1") (pinfunction "A_1") (pintype "passive"))
      (node (ref "R7") (pin "1") (pinfunction "1_1") (pintype "passive"))
    )
    (net (code "45") (name "Net-(LED6-A)") (class "Default")
      (node (ref "LED6") (pin "1") (pinfunction "A_1") (pintype "passive"))
      (node (ref "LED7") (pin "1") (pinfunction "A_1") (pintype "passive"))
      (node (ref "LED8") (pin "1") (pinfunction "A_1") (pintype "passive"))
      (node (ref "LED9") (pin "1") (pinfunction "A_1") (pintype "passive"))
      (node (ref "R5") (pin "1") (pinfunction "1_1") (pintype "passive"))
    )
    (net (code "46") (name "Net-(LED6-K)") (class "Default")
      (node (ref "LED6") (pin "2") (pinfunction "K_2") (pintype "passive"))
      (node (ref "LED7") (pin "2") (pinfunction "K_2") (pintype "passive"))
      (node (ref "LED8") (pin "2") (pinfunction "K_2") (pintype "passive"))
      (node (ref "LED9") (pin "2") (pinfunction "K_2") (pintype "passive"))
      (node (ref "Q2") (pin "3") (pinfunction "C_3") (pintype "passive"))
    )
    (net (code "47") (name "Net-(LED10-A)") (class "Default")
      (node (ref "LED10") (pin "1") (pinfunction "A_1") (pintype "passive"))
      (node (ref "LED11") (pin "1") (pinfunction "A_1") (pintype "passive"))
      (node (ref "LED12") (pin "1") (pinfunction "A_1") (pintype "passive"))
      (node (ref "LED13") (pin "1") (pinfunction "A_1") (pintype "passive"))
      (node (ref "R6") (pin "1") (pinfunction "1_1") (pintype "passive"))
    )
    (net (code "48") (name "Net-(LED10-K)") (class "Default")
      (node (ref "LED10") (pin "2") (pinfunction "K_2") (pintype "passive"))
      (node (ref "LED11") (pin "2") (pinfunction "K_2") (pintype "passive"))
      (node (ref "LED12") (pin "2") (pinfunction "K_2") (pintype "passive"))
      (node (ref "LED13") (pin "2") (pinfunction "K_2") (pintype "passive"))
      (node (ref "Q3") (pin "3") (pinfunction "C_3") (pintype "passive"))
    )
    (net (code "49") (name "Net-(LED14-A)") (class "Default")
      (node (ref "LED14") (pin "1") (pinfunction "A_1") (pintype "passive"))
      (node (ref "LED15") (pin "1") (pinfunction "A_1") (pintype "passive"))
      (node (ref "LED16") (pin "1") (pinfunction "A_1") (pintype "passive"))
      (node (ref "LED17") (pin "1") (pinfunction "A_1") (pintype "passive"))
      (node (ref "R8") (pin "1") (pinfunction "1_1") (pintype "passive"))
    )
    (net (code "50") (name "Net-(LED14-K)") (class "Default")
      (node (ref "LED14") (pin "2") (pinfunction "K_2") (pintype "passive"))
      (node (ref "LED15") (pin "2") (pinfunction "K_2") (pintype "passive"))
      (node (ref "LED16") (pin "2") (pinfunction "K_2") (pintype "passive"))
      (node (ref "LED17") (pin "2") (pinfunction "K_2") (pintype "passive"))
      (node (ref "Q5") (pin "3") (pinfunction "C_3") (pintype "passive"))
    )
    (net (code "51") (name "Net-(LED18-A)") (class "Default")
      (node (ref "LED18") (pin "1") (pinfunction "A_1") (pintype "passive"))
      (node (ref "LED19") (pin "1") (pinfunction "A_1") (pintype "passive"))
      (node (ref "LED20") (pin "1") (pinfunction "A_1") (pintype "passive"))
      (node (ref "LED21") (pin "1") (pinfunction "A_1") (pintype "passive"))
      (node (ref "R9") (pin "1") (pinfunction "1_1") (pintype "passive"))
    )
    (net (code "52") (name "Net-(LED18-K)") (class "Default")
      (node (ref "LED18") (pin "2") (pinfunction "K_2") (pintype "passive"))
      (node (ref "LED19") (pin "2") (pinfunction "K_2") (pintype "passive"))
      (node (ref "LED20") (pin "2") (pinfunction "K_2") (pintype "passive"))
      (node (ref "LED21") (pin "2") (pinfunction "K_2") (pintype "passive"))
      (node (ref "Q6") (pin "3") (pinfunction "C_3") (pintype "passive"))
    )
    (net (code "53") (name "Net-(LED22-K)") (class "Default")
      (node (ref "LED22") (pin "2") (pinfunction "K_2") (pintype "passive"))
      (node (ref "LED23") (pin "2") (pinfunction "K_2") (pintype "passive"))
      (node (ref "Q1") (pin "3") (pinfunction "C_3") (pintype "passive"))
    )
    (net (code "54") (name "Net-(LED23-A)") (class "Default")
      (node (ref "LED23") (pin "1") (pinfunction "A_1") (pintype "passive"))
      (node (ref "LED3") (pin "2") (pinfunction "K_2") (pintype "passive"))
    )
    (net (code "55") (name "Net-(LED24-A)") (class "Default")
      (node (ref "LED24") (pin "1") (pinfunction "A_1") (pintype "passive"))
      (node (ref "LED4") (pin "2") (pinfunction "K_2") (pintype "passive"))
    )
    (net (code "56") (name "Net-(LED24-K)") (class "Default")
      (node (ref "LED24") (pin "2") (pinfunction "K_2") (pintype "passive"))
      (node (ref "LED25") (pin "2") (pinfunction "K_2") (pintype "passive"))
      (node (ref "Q4") (pin "3") (pinfunction "C_3") (pintype "passive"))
    )
    (net (code "57") (name "Net-(LED25-A)") (class "Default")
      (node (ref "LED25") (pin "1") (pinfunction "A_1") (pintype "passive"))
      (node (ref "LED5") (pin "2") (pinfunction "K_2") (pintype "passive"))
    )
    (net (code "58") (name "Net-(LED26-K)") (class "Default")
      (node (ref "LED26") (pin "2") (pinfunction "K_2") (pintype "passive"))
      (node (ref "R13") (pin "1") (pinfunction "1_1") (pintype "passive"))
    )
    (net (code "59") (name "Net-(LED27-K)") (class "Default")
      (node (ref "LED27") (pin "2") (pinfunction "K_2") (pintype "passive"))
      (node (ref "R12") (pin "2") (pinfunction "2_2") (pintype "passive"))
    )
    (net (code "60") (name "Net-(LED28-K)") (class "Default")
      (node (ref "LED28") (pin "2") (pinfunction "K_2") (pintype "passive"))
      (node (ref "R14") (pin "2") (pinfunction "2_2") (pintype "passive"))
    )
    (net (code "61") (name "Net-(Q1-B)") (class "Default")
      (node (ref "Q1") (pin "1") (pinfunction "B_1") (pintype "passive"))
      (node (ref "R15") (pin "1") (pinfunction "1_1") (pintype "passive"))
    )
    (net (code "62") (name "Net-(Q2-B)") (class "Default")
      (node (ref "Q2") (pin "1") (pinfunction "B_1") (pintype "passive"))
      (node (ref "R16") (pin "1") (pinfunction "1_1") (pintype "passive"))
    )
    (net (code "63") (name "Net-(Q3-B)") (class "Default")
      (node (ref "Q3") (pin "1") (pinfunction "B_1") (pintype "passive"))
      (node (ref "R18") (pin "1") (pinfunction "1_1") (pintype "passive"))
    )
    (net (code "64") (name "Net-(Q4-B)") (class "Default")
      (node (ref "Q4") (pin "1") (pinfunction "B_1") (pintype "passive"))
      (node (ref "R17") (pin "1") (pinfunction "1_1") (pintype "passive"))
    )
    (net (code "65") (name "Net-(Q5-B)") (class "Default")
      (node (ref "Q5") (pin "1") (pinfunction "B_1") (pintype "passive"))
      (node (ref "R19") (pin "1") (pinfunction "1_1") (pintype "passive"))
    )
    (net (code "66") (name "Net-(Q6-B)") (class "Default")
      (node (ref "Q6") (pin "1") (pinfunction "B_1") (pintype "passive"))
      (node (ref "R20") (pin "1") (pinfunction "1_1") (pintype "passive"))
    )
    (net (code "67") (name "Net-(U1A-BOOT0)") (class "Default")
      (node (ref "R1") (pin "2") (pinfunction "2_2") (pintype "passive"))
      (node (ref "U1") (pin "44") (pinfunction "BOOT0_44") (pintype "input"))
    )
    (net (code "68") (name "Net-(U1A-NRST)") (class "Default")
      (node (ref "C1") (pin "2") (pinfunction "2_2") (pintype "passive"))
      (node (ref "R2") (pin "1") (pinfunction "1_1") (pintype "passive"))
      (node (ref "SW1") (pin "2") (pinfunction "2_2") (pintype "passive"))
      (node (ref "U1") (pin "7") (pinfunction "NRST_7") (pintype "bidirectional"))
    )
    (net (code "69") (name "Net-(U1A-PC13,_RTC_TAMP1,_RTC_TS,_RTC_OUT,_WKUP2)") (class "Default")
      (node (ref "R3") (pin "2") (pinfunction "2_2") (pintype "passive"))
      (node (ref "U1") (pin "2") (pinfunction "PC13,_RTC_TAMP1,_RTC_TS,_RTC_OUT,_WKUP2_2") (pintype "bidirectional"))
    )
    (net (code "70") (name "Net-(U1A-PF0-OSC_IN_(PF0),_OSC_IN)") (class "Default")
      (node (ref "C2") (pin "1") (pinfunction "1_1") (pintype "passive"))
      (node (ref "U1") (pin "5") (pinfunction "PF0-OSC_IN_(PF0),_OSC_IN_5") (pintype "bidirectional"))
      (node (ref "X1") (pin "2") (pinfunction "2_2") (pintype "passive"))
    )
    (net (code "71") (name "Net-(U1A-PF1-OSC_OUT_(PF1),_OSC_OUT)") (class "Default")
      (node (ref "C3") (pin "1") (pinfunction "1_1") (pintype "passive"))
      (node (ref "U1") (pin "6") (pinfunction "PF1-OSC_OUT_(PF1),_OSC_OUT_6") (pintype "bidirectional"))
      (node (ref "X1") (pin "1") (pinfunction "1_1") (pintype "passive"))
    )
    (net (code "72") (name "Net-(U1A-PF6)") (class "Default")
      (node (ref "SW2") (pin "1") (pinfunction "1_1") (pintype "passive"))
      (node (ref "SW2") (pin "4") (pinfunction "4_4") (pintype "passive"))
      (node (ref "U1") (pin "35") (pinfunction "PF6_35") (pintype "bidirectional"))
    )
    (net (code "73") (name "Net-(U1A-PF7)") (class "Default")
      (node (ref "SW3") (pin "1") (pinfunction "1_1") (pintype "passive"))
      (node (ref "SW3") (pin "4") (pinfunction "4_4") (pintype "passive"))
      (node (ref "U1") (pin "36") (pinfunction "PF7_36") (pintype "bidirectional"))
    )
    (net (code "74") (name "Net-(V1-VIN)") (class "Default")
      (node (ref "L1") (pin "2") (pinfunction "2_2") (pintype "passive"))
      (node (ref "V1") (pin "2") (pinfunction "VIN_2") (pintype "passive"))
    )
    (net (code "75") (name "V3.3") (class "Default")
      (node (ref "C13") (pin "2") (pinfunction "2_2") (pintype "passive"))
      (node (ref "C4") (pin "2") (pinfunction "2_2") (pintype "passive"))
      (node (ref "C5") (pin "2") (pinfunction "2_2") (pintype "passive"))
      (node (ref "C6") (pin "2") (pinfunction "2_2") (pintype "passive"))
      (node (ref "C7") (pin "2") (pinfunction "2_2") (pintype "passive"))
      (node (ref "JP1") (pin "2") (pinfunction "2_2") (pintype "passive"))
      (node (ref "JP6") (pin "1") (pinfunction "1_1") (pintype "passive"))
      (node (ref "JP7") (pin "2") (pinfunction "2_2") (pintype "passive"))
      (node (ref "LED1") (pin "1") (pinfunction "A_1") (pintype "passive"))
      (node (ref "R2") (pin "2") (pinfunction "2_2") (pintype "passive"))
      (node (ref "RI1") (pin "1") (pinfunction "1_1") (pintype "passive"))
      (node (ref "RI1") (pin "4") (pinfunction "4_4") (pintype "passive"))
      (node (ref "RI2") (pin "3") (pinfunction "3_3") (pintype "passive"))
      (node (ref "RI2") (pin "4") (pinfunction "4_4") (pintype "passive"))
      (node (ref "U1") (pin "1") (pinfunction "VBAT_1") (pintype "power_in"))
      (node (ref "U1") (pin "24") (pinfunction "VDD_24") (pintype "power_in"))
      (node (ref "U1") (pin "48") (pinfunction "VDD_48") (pintype "power_in"))
      (node (ref "U1") (pin "9") (pinfunction "VDDA_9") (pintype "power_in"))
      (node (ref "V2") (pin "3") (pinfunction "VOUT_3") (pintype "passive"))
    )
    (net (code "76") (name "VBAT") (class "Default")
      (node (ref "C10") (pin "2") (pinfunction "2_2") (pintype "passive"))
      (node (ref "L1") (pin "1") (pinfunction "1_1") (pintype "passive"))
      (node (ref "R10") (pin "2") (pinfunction "2_2") (pintype "passive"))
      (node (ref "S1") (pin "2") (pinfunction "2_2") (pintype "passive"))
    )
    (net (code "77") (name "VCC") (class "Default")
      (node (ref "D1") (pin "1") (pinfunction "A_1") (pintype "passive"))
      (node (ref "USB1") (pin "1") (pinfunction "+5V_1") (pintype "passive"))
    )
    (net (code "78") (name "unconnected-(S1-Pad3)") (class "Default")
      (node (ref "S1") (pin "3") (pinfunction "3_3") (pintype "passive"))
    )
    (net (code "79") (name "unconnected-(U1A-PB12,_TIM1_BKIN,_EVENTOUT-Pad25)") (class "Default")
      (node (ref "U1") (pin "25") (pinfunction "PB12,_TIM1_BKIN,_EVENTOUT_25") (pintype "bidirectional+no_connect"))
    )
    (net (code "80") (name "unconnected-(U1A-PC14-OSC32_IN_(PC14),_OSC32_IN-Pad3)") (class "Default")
      (node (ref "U1") (pin "3") (pinfunction "PC14-OSC32_IN_(PC14),_OSC32_IN_3") (pintype "bidirectional+no_connect"))
    )
    (net (code "81") (name "unconnected-(U1A-PC15-OSC32_OUT_(PC15),_OSC32_OUT-Pad4)") (class "Default")
      (node (ref "U1") (pin "4") (pinfunction "PC15-OSC32_OUT_(PC15),_OSC32_OUT_4") (pintype "bidirectional+no_connect"))
    )
    (net (code "82") (name "unconnected-(USB1-D+-Pad3)") (class "Default")
      (node (ref "USB1") (pin "3") (pinfunction "D+_3") (pintype "passive"))
    )
    (net (code "83") (name "unconnected-(USB1-D--Pad2)") (class "Default")
      (node (ref "USB1") (pin "2") (pinfunction "D-_2") (pintype "passive"))
    )
    (net (code "84") (name "unconnected-(USB1-ID-Pad4)") (class "Default")
      (node (ref "USB1") (pin "4") (pinfunction "ID_4") (pintype "passive"))
    )
  )
)
